# bottomboard.net
KiCad netlist of a schematic drawn in EAGLE
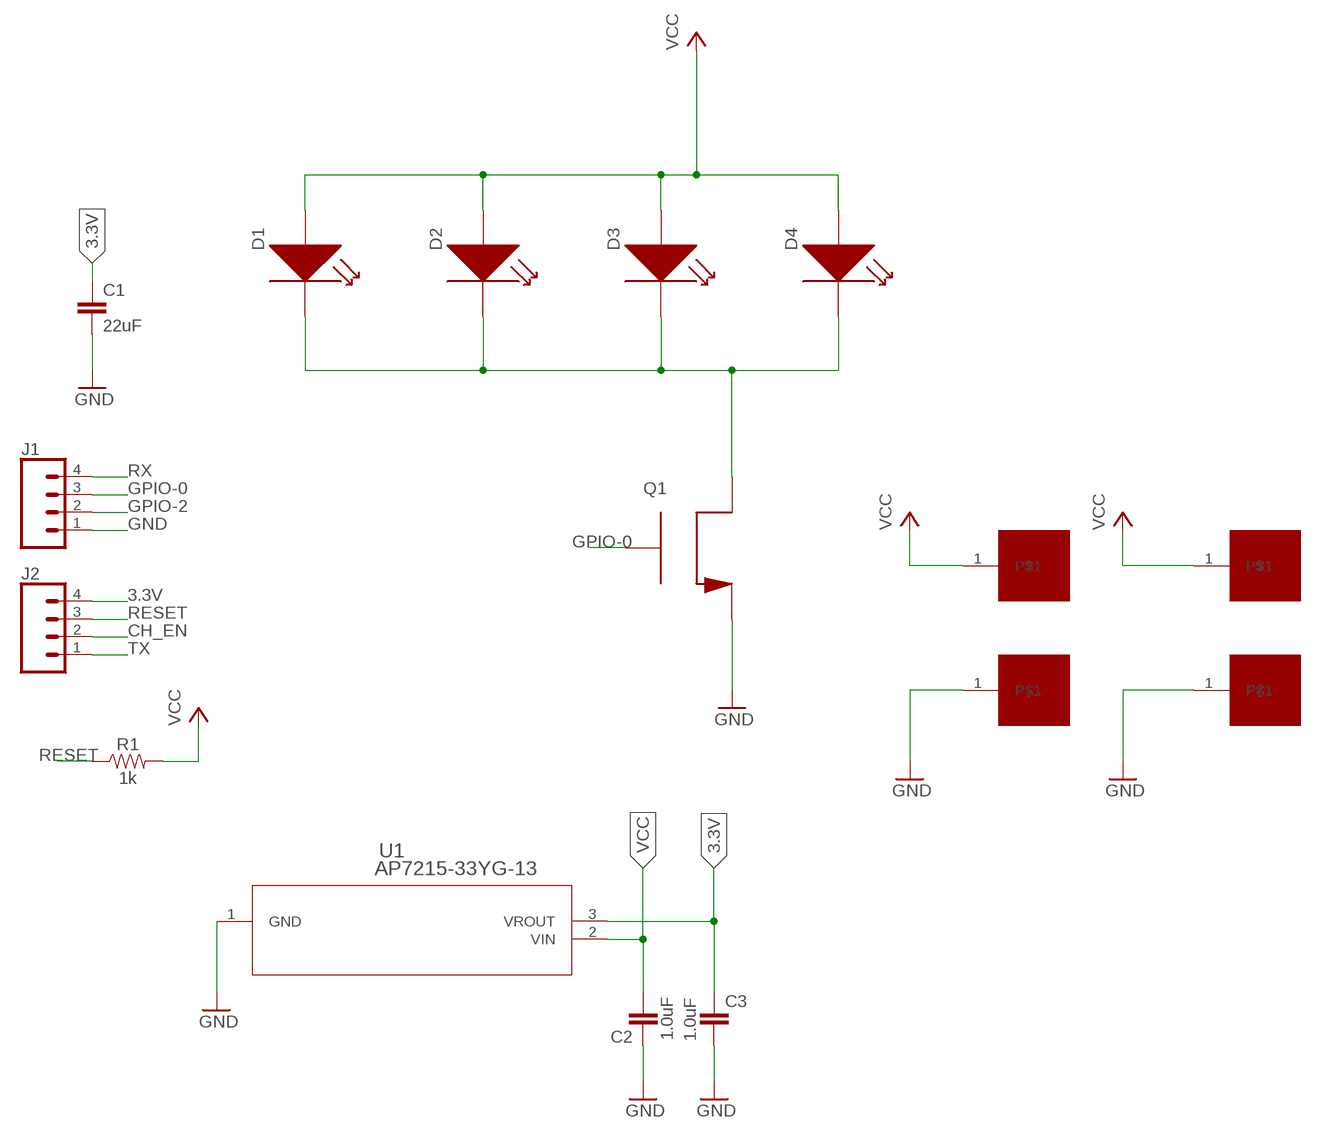
[diagram p0: schematic, sheet 1]

(export (version "E")
  (design (tool "Eeschema 10.0.6"))
  (components
    (comp (ref "C1")
      (value "22uF")
      (footprint "eagle-import:0805")
      (libsource (lib "eagle-import") (part "22UF-0805-6.3V-20%"))
    )
    (comp (ref "C2")
      (value "1.0uF")
      (footprint "eagle-import:0402")
      (libsource (lib "eagle-import") (part "1.0UF-0402-16V-10%"))
    )
    (comp (ref "C3")
      (value "1.0uF")
      (footprint "eagle-import:0402")
      (libsource (lib "eagle-import") (part "1.0UF-0402-16V-10%"))
    )
    (comp (ref "D1")
      (value "NVSLE21AT")
      (footprint "eagle-import:NVSLE21AT")
      (libsource (lib "eagle-import") (part "NVSLE21AT"))
    )
    (comp (ref "D2")
      (value "NVSLE21AT")
      (footprint "eagle-import:NVSLE21AT")
      (libsource (lib "eagle-import") (part "NVSLE21AT"))
    )
    (comp (ref "D3")
      (value "NVSLE21AT")
      (footprint "eagle-import:NVSLE21AT")
      (libsource (lib "eagle-import") (part "NVSLE21AT"))
    )
    (comp (ref "D4")
      (value "NVSLE21AT")
      (footprint "eagle-import:NVSLE21AT")
      (libsource (lib "eagle-import") (part "NVSLE21AT"))
    )
    (comp (ref "J1")
      (value "CONN_04")
      (footprint "eagle-import:1X04")
      (libsource (lib "eagle-import") (part "CONN_04"))
    )
    (comp (ref "J2")
      (value "CONN_04")
      (footprint "eagle-import:1X04")
      (libsource (lib "eagle-import") (part "CONN_04"))
    )
    (comp (ref "P1")
      (value "PAD")
      (footprint "eagle-import:PAD")
      (libsource (lib "eagle-import") (part "PAD"))
    )
    (comp (ref "P2")
      (value "PAD")
      (footprint "eagle-import:PAD")
      (libsource (lib "eagle-import") (part "PAD"))
    )
    (comp (ref "P3")
      (value "PAD")
      (footprint "eagle-import:PAD")
      (libsource (lib "eagle-import") (part "PAD"))
    )
    (comp (ref "P4")
      (value "PAD")
      (footprint "eagle-import:PAD")
      (libsource (lib "eagle-import") (part "PAD"))
    )
    (comp (ref "Q1")
      (value "SIA436DJ")
      (footprint "eagle-import:POWERPAK_SC70-6L")
      (libsource (lib "eagle-import") (part "SIA436DJ"))
    )
    (comp (ref "R1")
      (value "1k")
      (footprint "eagle-import:0603")
      (libsource (lib "eagle-import") (part "1KOHM-0603-1/10W-1%"))
    )
    (comp (ref "U1")
      (value "AP7215-33YG-13")
      (footprint "eagle-import:SOT89-3L")
      (fields (field (name "MANUFACTURER_PART_NUMBER") "AP721533YG13"))
      (libsource (lib "eagle-import") (part "AP7215-33YG-13"))
    )
  )
  (nets
    (net (code "1") (name "/CH_EN") (class "Default")
      (node (ref "J2") (pin "2") (pinfunction "2_2") (pintype "passive"))
    )
    (net (code "2") (name "/GPIO-0") (class "Default")
      (node (ref "J1") (pin "3") (pinfunction "3_3") (pintype "passive"))
      (node (ref "Q1") (pin "P$4") (pinfunction "G_P$4") (pintype "bidirectional"))
    )
    (net (code "3") (name "/GPIO-2") (class "Default")
      (node (ref "J1") (pin "2") (pinfunction "2_2") (pintype "passive"))
    )
    (net (code "4") (name "/RESET") (class "Default")
      (node (ref "J2") (pin "3") (pinfunction "3_3") (pintype "passive"))
      (node (ref "R1") (pin "1") (pinfunction "1_1") (pintype "passive"))
    )
    (net (code "5") (name "/RX") (class "Default")
      (node (ref "J1") (pin "4") (pinfunction "4_4") (pintype "passive"))
    )
    (net (code "6") (name "/TX") (class "Default")
      (node (ref "J2") (pin "1") (pinfunction "1_1") (pintype "passive"))
    )
    (net (code "7") (name "3.3V") (class "Default")
      (node (ref "C1") (pin "1") (pinfunction "1_1") (pintype "passive"))
      (node (ref "C3") (pin "1") (pinfunction "1_1") (pintype "passive"))
      (node (ref "J2") (pin "4") (pinfunction "4_4") (pintype "passive"))
      (node (ref "U1") (pin "3") (pinfunction "VROUT_3") (pintype "output"))
    )
    (net (code "8") (name "GND") (class "Default")
      (node (ref "C1") (pin "2") (pinfunction "2_2") (pintype "passive"))
      (node (ref "C2") (pin "1") (pinfunction "1_1") (pintype "passive"))
      (node (ref "C3") (pin "2") (pinfunction "2_2") (pintype "passive"))
      (node (ref "J1") (pin "1") (pinfunction "1_1") (pintype "passive"))
      (node (ref "P2") (pin "1") (pinfunction "P$1_1") (pintype "bidirectional"))
      (node (ref "P4") (pin "1") (pinfunction "P$1_1") (pintype "bidirectional"))
      (node (ref "Q1") (pin "P$2") (pinfunction "S_P$2") (pintype "bidirectional"))
      (node (ref "Q1") (pin "P$3") (pinfunction "S_P$3") (pintype "bidirectional"))
      (node (ref "U1") (pin "1") (pinfunction "GND_1") (pintype "power_in"))
    )
    (net (code "9") (name "Net-(D1-CATHODE)") (class "Default")
      (node (ref "D1") (pin "P$1") (pinfunction "CATHODE_P$1") (pintype "bidirectional"))
      (node (ref "D2") (pin "P$1") (pinfunction "CATHODE_P$1") (pintype "bidirectional"))
      (node (ref "D3") (pin "P$1") (pinfunction "CATHODE_P$1") (pintype "bidirectional"))
      (node (ref "D4") (pin "P$1") (pinfunction "CATHODE_P$1") (pintype "bidirectional"))
      (node (ref "Q1") (pin "P$1") (pinfunction "D_P$1") (pintype "bidirectional"))
      (node (ref "Q1") (pin "P$5") (pinfunction "D_P$5") (pintype "bidirectional"))
      (node (ref "Q1") (pin "P$6") (pinfunction "D_P$6") (pintype "bidirectional"))
      (node (ref "Q1") (pin "P$7") (pinfunction "D_P$7") (pintype "bidirectional"))
      (node (ref "Q1") (pin "P$8") (pinfunction "D_P$8") (pintype "bidirectional"))
    )
    (net (code "10") (name "VCC") (class "Default")
      (node (ref "C2") (pin "2") (pinfunction "2_2") (pintype "passive"))
      (node (ref "D1") (pin "P$2") (pinfunction "ANODE_P$2") (pintype "bidirectional"))
      (node (ref "D2") (pin "P$2") (pinfunction "ANODE_P$2") (pintype "bidirectional"))
      (node (ref "D3") (pin "P$2") (pinfunction "ANODE_P$2") (pintype "bidirectional"))
      (node (ref "D4") (pin "P$2") (pinfunction "ANODE_P$2") (pintype "bidirectional"))
      (node (ref "P1") (pin "1") (pinfunction "P$1_1") (pintype "bidirectional"))
      (node (ref "P3") (pin "1") (pinfunction "P$1_1") (pintype "bidirectional"))
      (node (ref "R1") (pin "2") (pinfunction "2_2") (pintype "passive"))
      (node (ref "U1") (pin "2") (pinfunction "VIN_2") (pintype "input"))
    )
  )
)
